# front.net
KiCad netlist of a schematic drawn in EAGLE
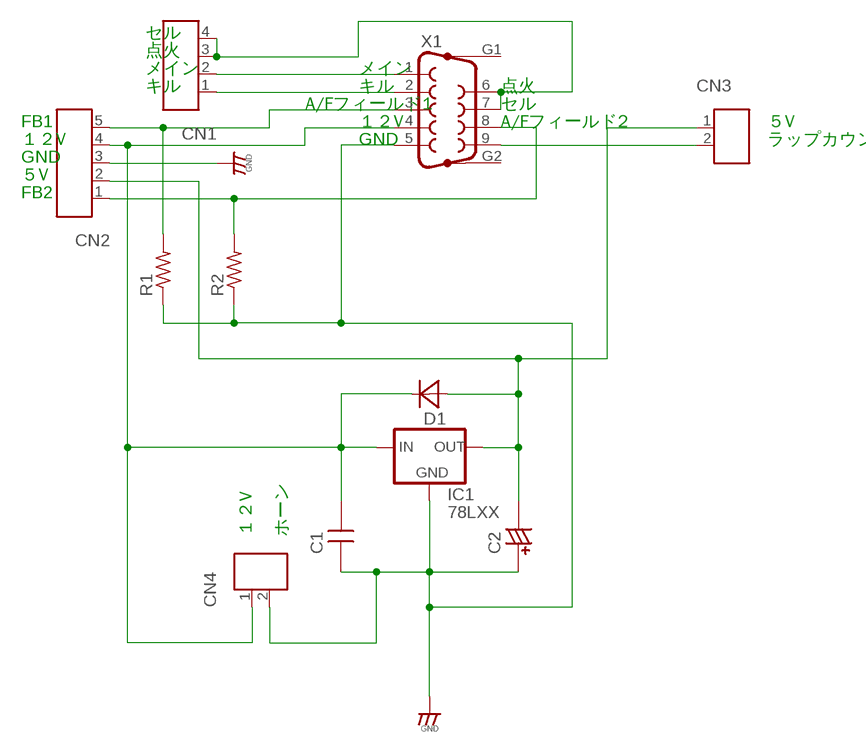
[diagram p0: schematic, sheet 1]

(export (version "E")
  (design (tool "Eeschema 10.0.6"))
  (components
    (comp (ref "C1")
      (value "CAPDIP_1")
      (footprint "eagle-import:CAP_DIP_1")
      (libsource (lib "eagle-import") (part "CAPDIP_1"))
    )
    (comp (ref "C2")
      (value "CCAP6.5")
      (footprint "eagle-import:CCAP_6.5")
      (libsource (lib "eagle-import") (part "CCAP6.5"))
    )
    (comp (ref "CN1")
      (value "CON_4P")
      (footprint "eagle-import:CON_HRS_DIP_4")
      (libsource (lib "eagle-import") (part "CON_4P"))
    )
    (comp (ref "CN2")
      (value "CON_5P")
      (footprint "eagle-import:CON_HRS_DIP_5")
      (libsource (lib "eagle-import") (part "CON_5P"))
    )
    (comp (ref "CN3")
      (value "CON_2P")
      (footprint "eagle-import:CON_HRS_DIP_2")
      (libsource (lib "eagle-import") (part "CON_2P"))
    )
    (comp (ref "CN4")
      (value "CON_2P")
      (footprint "eagle-import:CON_HRS_DIP_2")
      (libsource (lib "eagle-import") (part "CON_2P"))
    )
    (comp (ref "D1")
      (value "DIODEGENERIC_2")
      (footprint "eagle-import:DIODE_2")
      (libsource (lib "eagle-import") (part "DIODEGENERIC_2"))
    )
    (comp (ref "IC1")
      (value "78LXX")
      (footprint "eagle-import:TO92-VREG-78L")
      (libsource (lib "eagle-import") (part "78LXX"))
    )
    (comp (ref "R1")
      (value "R-US_0207/7")
      (footprint "eagle-import:0207_7")
      (libsource (lib "eagle-import") (part "R-US_0207/7"))
    )
    (comp (ref "R2")
      (value "R-US_0207/7")
      (footprint "eagle-import:0207_7")
      (libsource (lib "eagle-import") (part "R-US_0207/7"))
    )
    (comp (ref "X1")
      (value "F09HP")
      (footprint "eagle-import:F09HP")
      (libsource (lib "eagle-import") (part "F09HP"))
    )
  )
  (nets
    (net (code "1") (name "GND") (class "Default")
      (node (ref "C1") (pin "1") (pinfunction "1_1") (pintype "passive"))
      (node (ref "C2") (pin "+") (pinfunction "+_+") (pintype "passive"))
      (node (ref "CN2") (pin "3") (pinfunction "3_3") (pintype "passive"))
      (node (ref "CN4") (pin "2") (pinfunction "2_2") (pintype "passive"))
      (node (ref "IC1") (pin "G") (pinfunction "GND_G") (pintype "input"))
      (node (ref "R1") (pin "1") (pinfunction "1_1") (pintype "passive"))
      (node (ref "R2") (pin "1") (pinfunction "1_1") (pintype "passive"))
      (node (ref "X1") (pin "5") (pinfunction "5_5") (pintype "passive"))
    )
    (net (code "2") (name "Net-(CN1-Pad1)") (class "Default")
      (node (ref "CN1") (pin "1") (pinfunction "1_1") (pintype "passive"))
      (node (ref "X1") (pin "2") (pinfunction "2_2") (pintype "passive"))
    )
    (net (code "3") (name "Net-(CN1-Pad2)") (class "Default")
      (node (ref "CN1") (pin "2") (pinfunction "2_2") (pintype "passive"))
      (node (ref "X1") (pin "1") (pinfunction "1_1") (pintype "passive"))
    )
    (net (code "4") (name "Net-(CN1-Pad3)") (class "Default")
      (node (ref "CN1") (pin "3") (pinfunction "3_3") (pintype "passive"))
      (node (ref "CN1") (pin "4") (pinfunction "4_4") (pintype "passive"))
      (node (ref "X1") (pin "6") (pinfunction "6_6") (pintype "passive"))
      (node (ref "X1") (pin "7") (pinfunction "7_7") (pintype "passive"))
    )
    (net (code "5") (name "Net-(CN2-Pad1)") (class "Default")
      (node (ref "CN2") (pin "1") (pinfunction "1_1") (pintype "passive"))
      (node (ref "R2") (pin "2") (pinfunction "2_2") (pintype "passive"))
      (node (ref "X1") (pin "8") (pinfunction "8_8") (pintype "passive"))
    )
    (net (code "6") (name "Net-(CN2-Pad5)") (class "Default")
      (node (ref "CN2") (pin "5") (pinfunction "5_5") (pintype "passive"))
      (node (ref "R1") (pin "2") (pinfunction "2_2") (pintype "passive"))
      (node (ref "X1") (pin "3") (pinfunction "3_3") (pintype "passive"))
    )
    (net (code "7") (name "Net-(CN3-Pad2)") (class "Default")
      (node (ref "CN3") (pin "2") (pinfunction "2_2") (pintype "passive"))
      (node (ref "X1") (pin "9") (pinfunction "9_9") (pintype "passive"))
    )
    (net (code "8") (name "Net-(IC1-IN)") (class "Default")
      (node (ref "C1") (pin "2") (pinfunction "2_2") (pintype "passive"))
      (node (ref "CN2") (pin "4") (pinfunction "4_4") (pintype "passive"))
      (node (ref "CN4") (pin "1") (pinfunction "1_1") (pintype "passive"))
      (node (ref "D1") (pin "K") (pinfunction "K_K") (pintype "passive"))
      (node (ref "IC1") (pin "I") (pinfunction "IN_I") (pintype "input"))
      (node (ref "X1") (pin "4") (pinfunction "4_4") (pintype "passive"))
    )
    (net (code "9") (name "Net-(IC1-OUT)") (class "Default")
      (node (ref "C2") (pin "-") (pinfunction "-_-") (pintype "passive"))
      (node (ref "CN2") (pin "2") (pinfunction "2_2") (pintype "passive"))
      (node (ref "CN3") (pin "1") (pinfunction "1_1") (pintype "passive"))
      (node (ref "D1") (pin "A") (pinfunction "A_A") (pintype "passive"))
      (node (ref "IC1") (pin "O") (pinfunction "OUT_O") (pintype "passive"))
    )
    (net (code "10") (name "unconnected-(X1-PadG1)") (class "Default")
      (node (ref "X1") (pin "G1") (pinfunction "G1_G1") (pintype "passive"))
    )
    (net (code "11") (name "unconnected-(X1-PadG2)") (class "Default")
      (node (ref "X1") (pin "G2") (pinfunction "G2_G2") (pintype "passive"))
    )
  )
)
